# lightampSMT.net
KiCad netlist of a schematic drawn in EAGLE
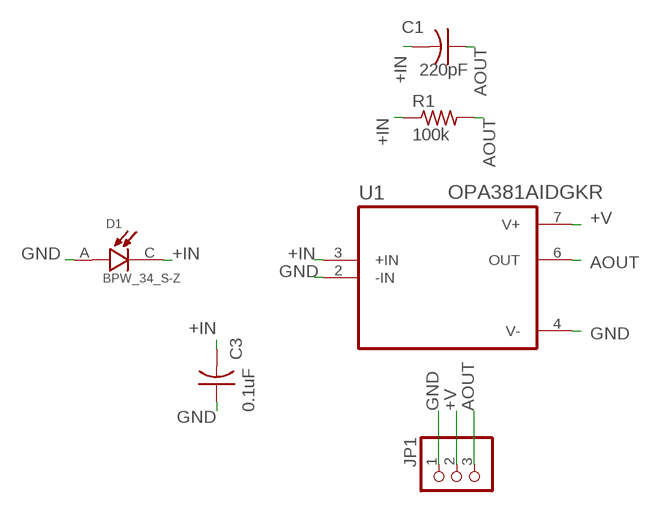
[diagram p0: schematic, sheet 1]

(export (version "E")
  (design (tool "Eeschema 10.0.6"))
  (components
    (comp (ref "C1")
      (value "220pF")
      (footprint "eagle-import:C0603K")
      (libsource (lib "eagle-import") (part "C-USC0603K"))
    )
    (comp (ref "C3")
      (value "0.1uF")
      (footprint "eagle-import:C0603K")
      (libsource (lib "eagle-import") (part "C-USC0603K"))
    )
    (comp (ref "D1")
      (value "BPW_34_S-Z")
      (footprint "eagle-import:DIO_BPW_34_S-Z")
      (fields (field (name "MF") "OSRAM Opto") (field (name "MP") "BPW 34 S-Z"))
      (libsource (lib "eagle-import") (part "BPW_34_S-Z"))
    )
    (comp (ref "JP1")
      (value "PINHD-1X3")
      (footprint "eagle-import:1X03")
      (libsource (lib "eagle-import") (part "PINHD-1X3"))
    )
    (comp (ref "R1")
      (value "100k")
      (footprint "eagle-import:R0603")
      (libsource (lib "eagle-import") (part "R-US_R0603"))
    )
    (comp (ref "U1")
      (value "OPA381AIDGKR")
      (footprint "eagle-import:SOP65P490X110-8N")
      (fields (field (name "MF") "Texas Instruments"))
      (libsource (lib "eagle-import") (part "OPA381AIDGKR"))
    )
  )
  (nets
    (net (code "1") (name "/+IN") (class "Default")
      (node (ref "C1") (pin "2") (pinfunction "2_2") (pintype "passive"))
      (node (ref "C3") (pin "2") (pinfunction "2_2") (pintype "passive"))
      (node (ref "D1") (pin "C") (pinfunction "C_C") (pintype "passive"))
      (node (ref "R1") (pin "1") (pinfunction "1_1") (pintype "passive"))
      (node (ref "U1") (pin "3") (pinfunction "+IN_3") (pintype "input"))
    )
    (net (code "2") (name "/+V") (class "Default")
      (node (ref "JP1") (pin "2") (pinfunction "2_2") (pintype "passive"))
      (node (ref "U1") (pin "7") (pinfunction "V+_7") (pintype "power_in"))
    )
    (net (code "3") (name "/AOUT") (class "Default")
      (node (ref "C1") (pin "1") (pinfunction "1_1") (pintype "passive"))
      (node (ref "JP1") (pin "3") (pinfunction "3_3") (pintype "passive"))
      (node (ref "R1") (pin "2") (pinfunction "2_2") (pintype "passive"))
      (node (ref "U1") (pin "6") (pinfunction "OUT_6") (pintype "output"))
    )
    (net (code "4") (name "/GND") (class "Default")
      (node (ref "C3") (pin "1") (pinfunction "1_1") (pintype "passive"))
      (node (ref "D1") (pin "A") (pinfunction "A_A") (pintype "passive"))
      (node (ref "JP1") (pin "1") (pinfunction "1_1") (pintype "passive"))
      (node (ref "U1") (pin "2") (pinfunction "-IN_2") (pintype "input"))
      (node (ref "U1") (pin "4") (pinfunction "V-_4") (pintype "power_in"))
    )
  )
)
